# throughhole.net
KiCad netlist of a schematic drawn in EAGLE
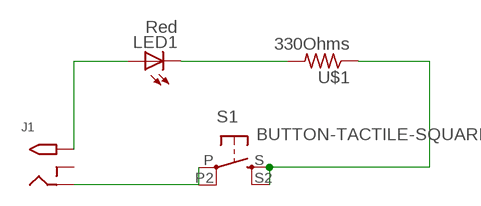
[diagram p0: schematic, sheet 1]

(export (version "E")
  (design (tool "Eeschema 10.0.6"))
  (components
    (comp (ref "J1")
      (value "2.1MMJACKTHM")
      (footprint "eagle-import:PJ-102A")
      (libsource (lib "eagle-import") (part "2.1MMJACKTHM"))
    )
    (comp (ref "LED1")
      (value "Red")
      (footprint "eagle-import:LED5MM")
      (libsource (lib "eagle-import") (part "LED5MM"))
    )
    (comp (ref "S1")
      (value "BUTTON-TACTILE-SQUARE")
      (footprint "eagle-import:BUTTON-TACTILE-SQUARE-ADAFRUIT1010")
      (libsource (lib "eagle-import") (part "BUTTON-TACTILE-SQUARE"))
    )
    (comp (ref "U$1")
      (value "330Ohms")
      (footprint "eagle-import:RESAD1160W55L680D260_HS")
      (libsource (lib "eagle-import") (part "RESISTORTH-1/4W-CARBON"))
    )
  )
  (nets
    (net (code "1") (name "Net-(J1-PadTIP)") (class "Default")
      (node (ref "J1") (pin "TIP") (pinfunction "TIP_TIP") (pintype "bidirectional"))
      (node (ref "LED1") (pin "A") (pinfunction "A_A") (pintype "passive"))
    )
    (net (code "2") (name "Net-(LED1-C)") (class "Default")
      (node (ref "LED1") (pin "K") (pinfunction "C_K") (pintype "passive"))
      (node (ref "U$1") (pin "2") (pinfunction "2_2") (pintype "passive"))
    )
    (net (code "3") (name "Net-(S1-P1)") (class "Default")
      (node (ref "J1") (pin "RING") (pinfunction "RING_RING") (pintype "bidirectional"))
      (node (ref "S1") (pin "P") (pinfunction "P_P") (pintype "passive"))
      (node (ref "S1") (pin "P2") (pinfunction "P1_P2") (pintype "passive"))
    )
    (net (code "4") (name "Net-(S1-S1)") (class "Default")
      (node (ref "S1") (pin "S") (pinfunction "S_S") (pintype "passive"))
      (node (ref "S1") (pin "S2") (pinfunction "S1_S2") (pintype "passive"))
      (node (ref "U$1") (pin "1") (pinfunction "1_1") (pintype "passive"))
    )
    (net (code "5") (name "unconnected-(J1-PadRING_SW)") (class "Default")
      (node (ref "J1") (pin "RING_SW") (pinfunction "RING_SW_RING_SW") (pintype "bidirectional"))
    )
  )
)
